# robot_lfy.net
KiCad netlist of a schematic drawn in Altium Designer
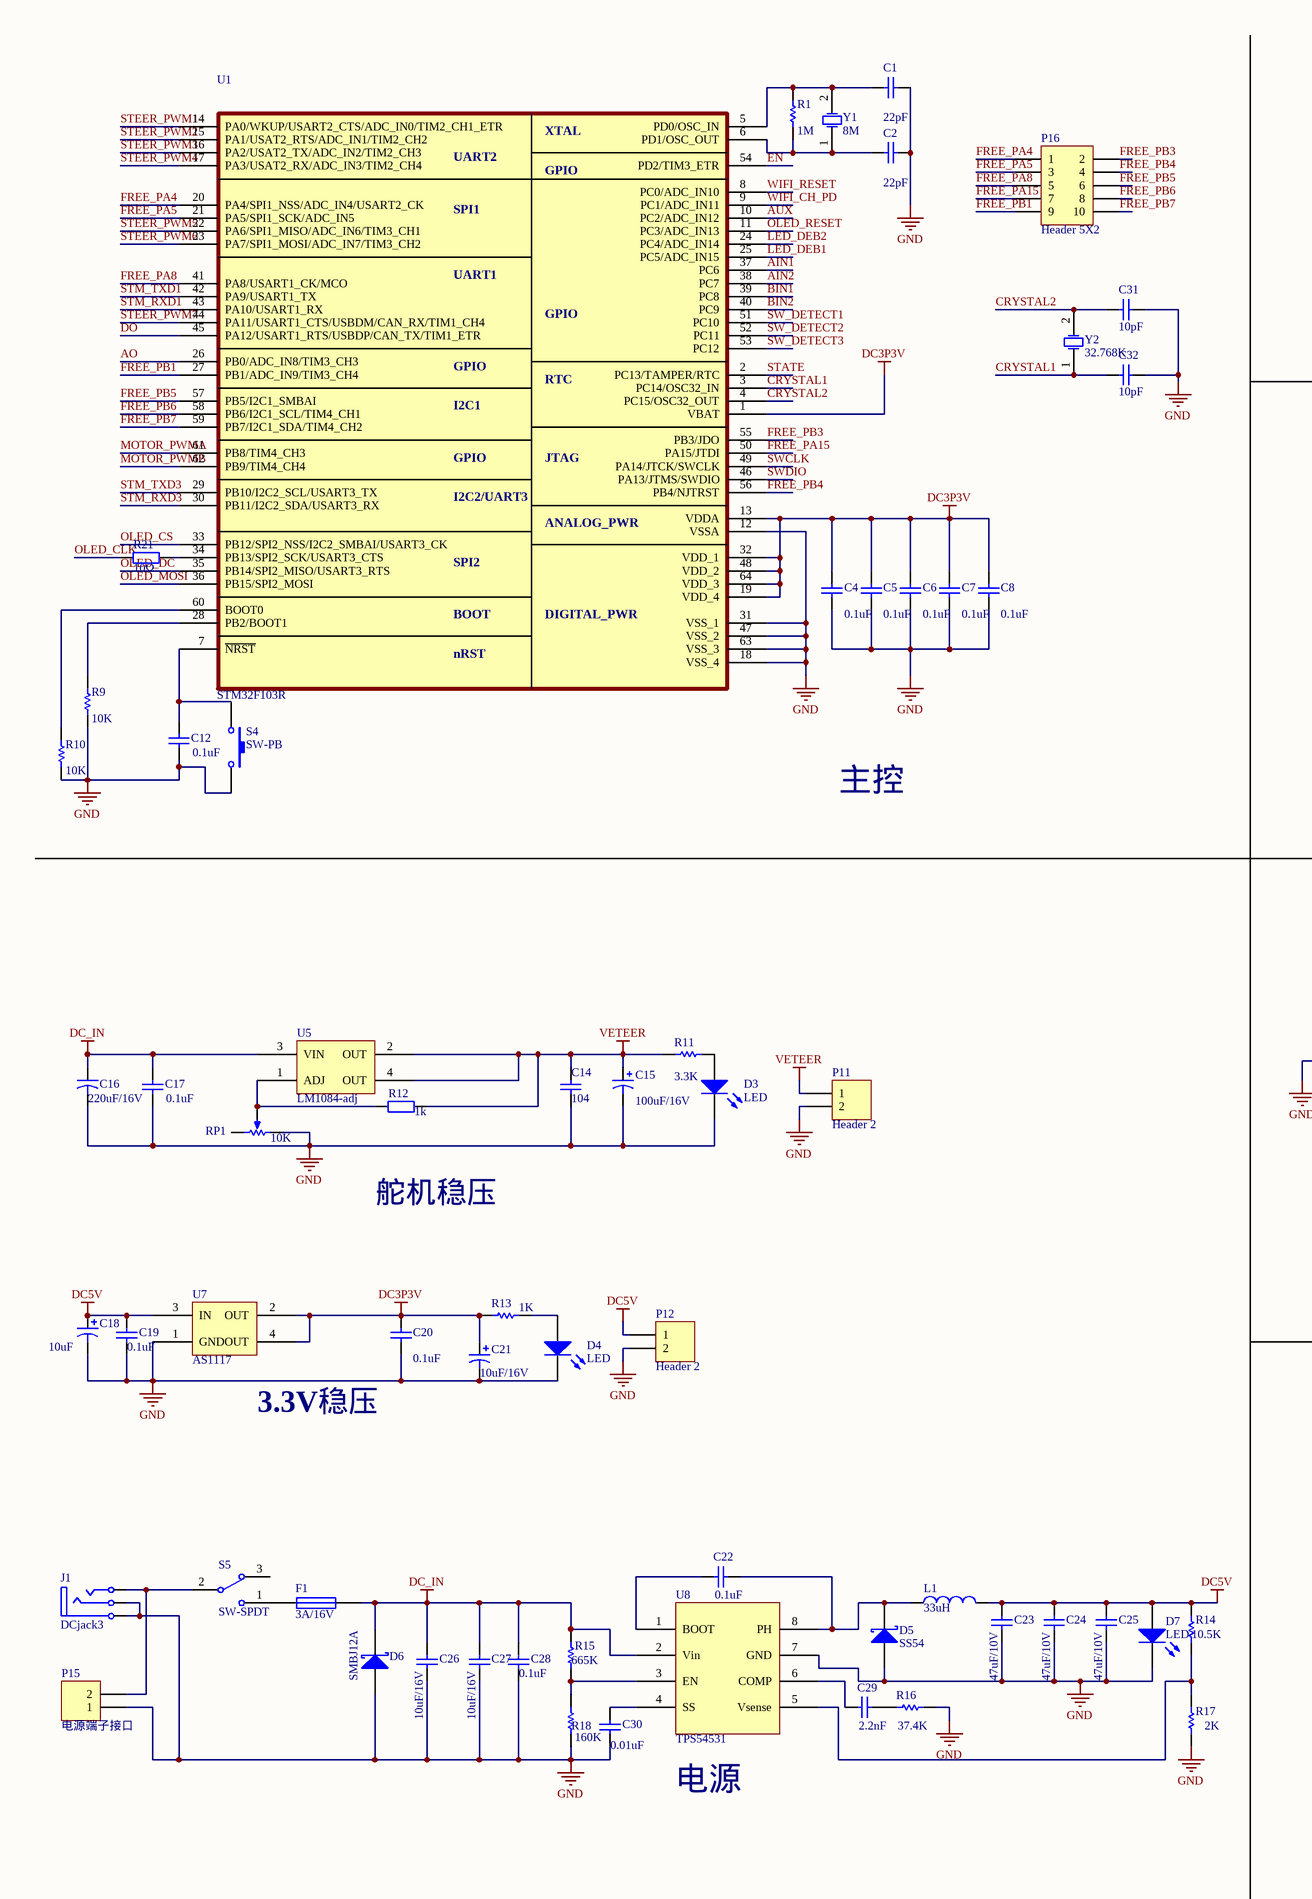
[diagram p0: robot_lfy.SchDoc, left]
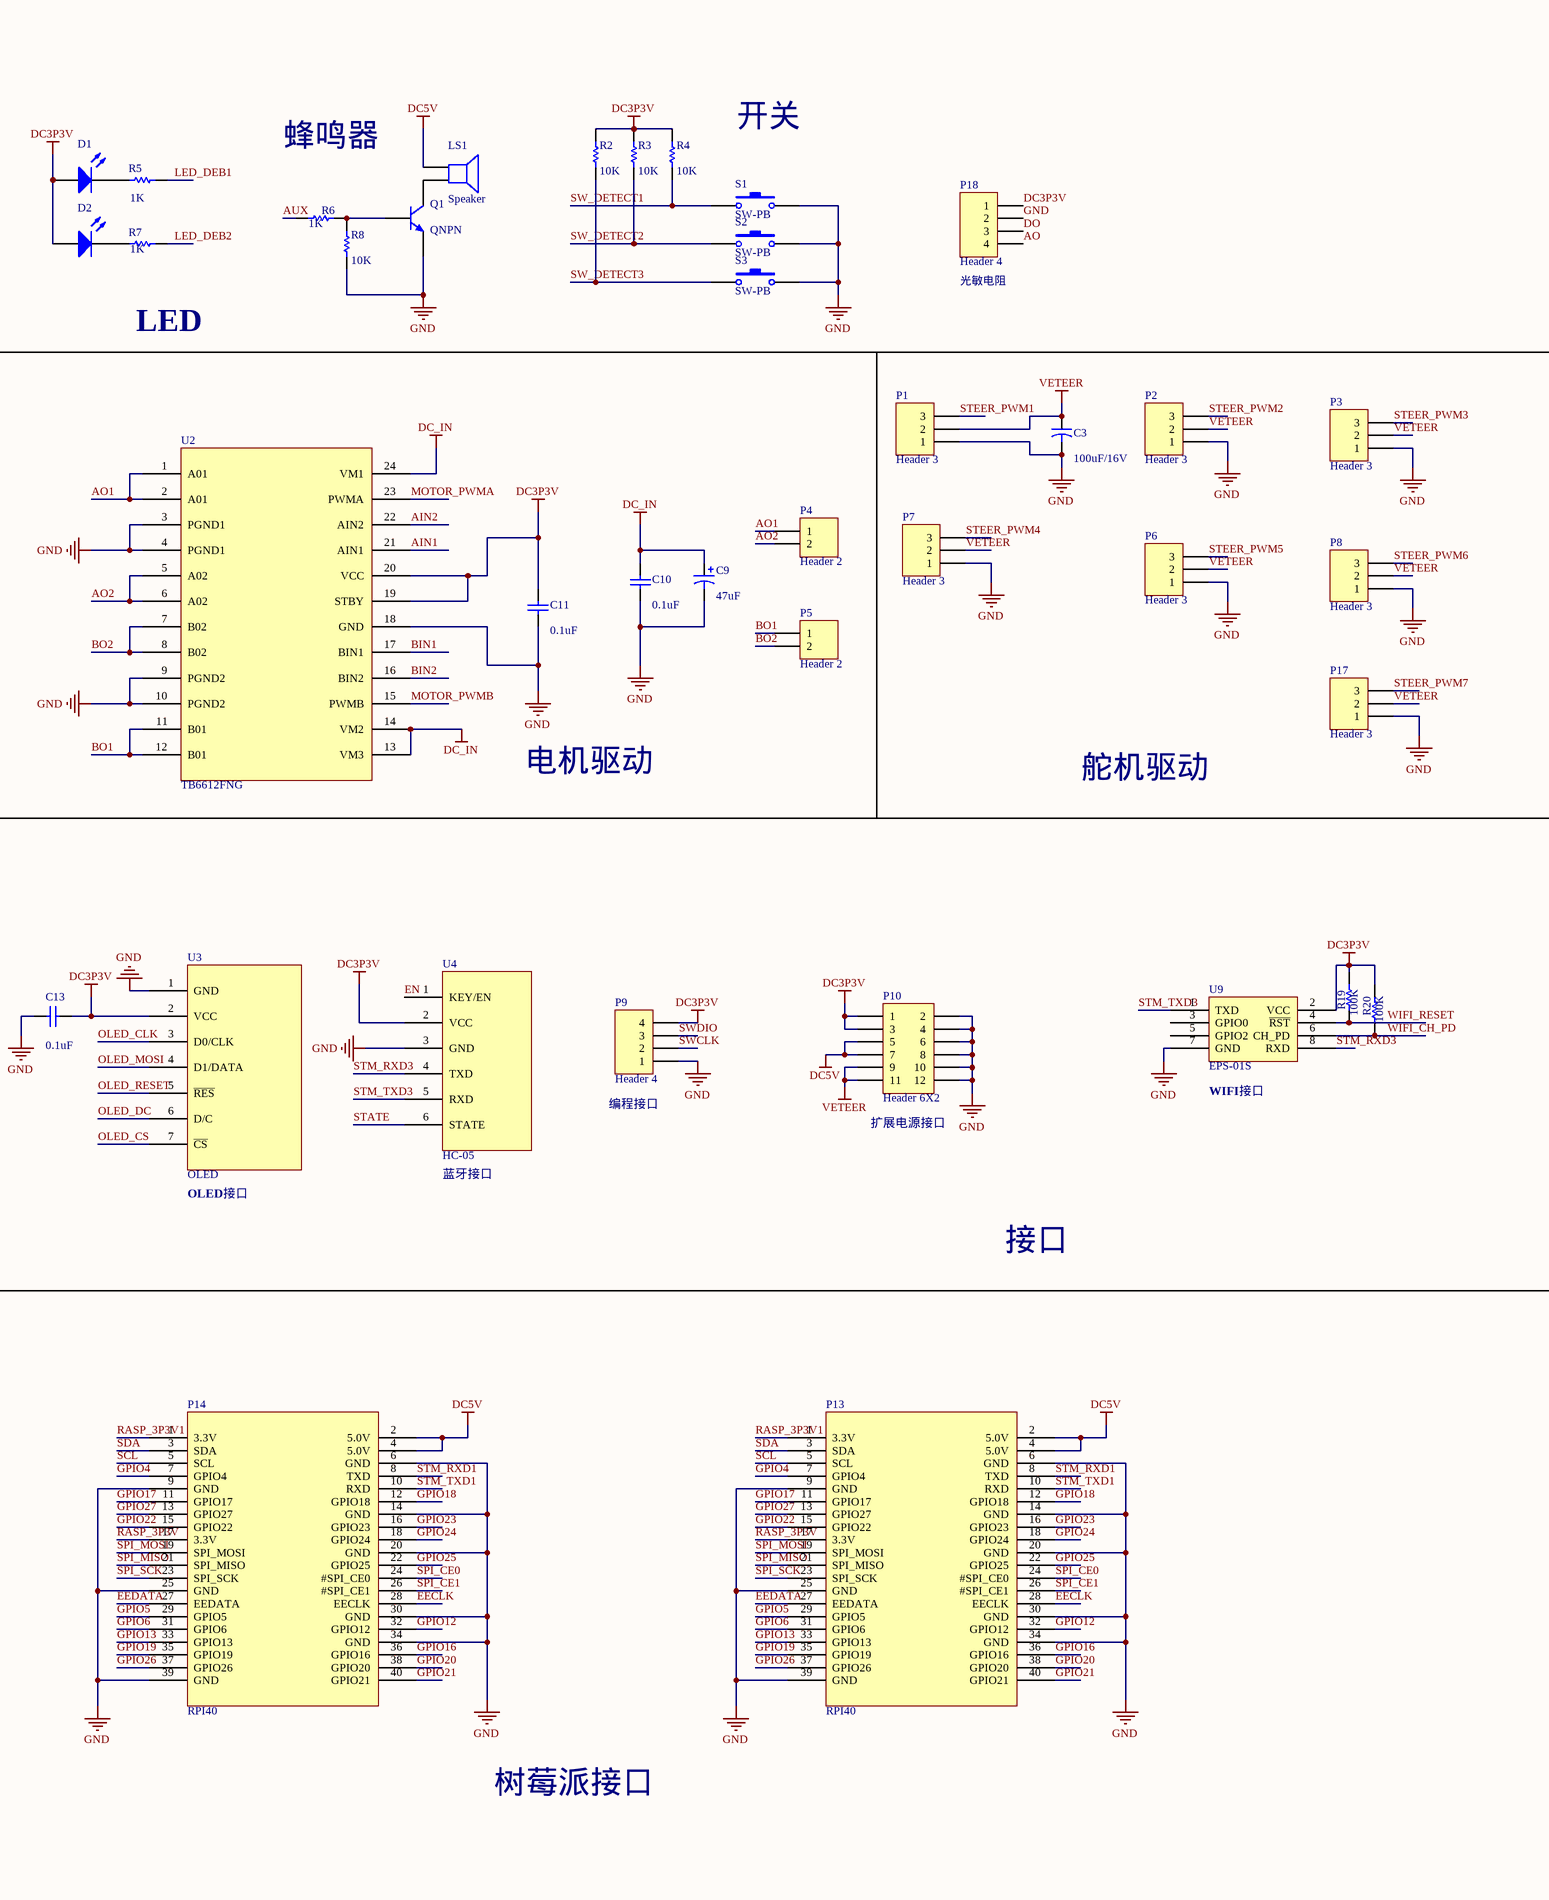
[diagram p1: robot_lfy.SchDoc, right]

(export (version "E")
  (design (tool "Eeschema 10.0.6"))
  (components
    (comp (ref "C1")
      (value "22pF")
      (footprint "LC-0805_C")
      (description "Capacitor")
      (fields (field (name "PUBLISHER") "Altium Limited"))
      (libsource (lib "Miscellaneous Devices") (part "Cap"))
    )
    (comp (ref "C2")
      (value "22pF")
      (footprint "LC-0805_C")
      (description "Capacitor")
      (fields (field (name "PUBLISHER") "Altium Limited"))
      (libsource (lib "Miscellaneous Devices") (part "Cap"))
    )
    (comp (ref "C3")
      (value "100uF/16V")
      (footprint "CM D(6.3*7.7)")
      (description "Capacitor")
      (fields (field (name "PUBLISHER") "Altium Limited"))
      (libsource (lib "Miscellaneous Devices") (part "Cap2"))
    )
    (comp (ref "C4")
      (value "0.1uF")
      (footprint "LC-0805_C")
      (description "Capacitor")
      (fields (field (name "PUBLISHER") "Altium Limited"))
      (libsource (lib "Miscellaneous Devices") (part "Cap"))
    )
    (comp (ref "C5")
      (value "0.1uF")
      (footprint "LC-0805_C")
      (description "Capacitor")
      (fields (field (name "PUBLISHER") "Altium Limited"))
      (libsource (lib "Miscellaneous Devices") (part "Cap"))
    )
    (comp (ref "C6")
      (value "0.1uF")
      (footprint "LC-0805_C")
      (description "Capacitor")
      (fields (field (name "PUBLISHER") "Altium Limited"))
      (libsource (lib "Miscellaneous Devices") (part "Cap"))
    )
    (comp (ref "C7")
      (value "0.1uF")
      (footprint "LC-0805_C")
      (description "Capacitor")
      (fields (field (name "PUBLISHER") "Altium Limited"))
      (libsource (lib "Miscellaneous Devices") (part "Cap"))
    )
    (comp (ref "C8")
      (value "0.1uF")
      (footprint "LC-0805_C")
      (description "Capacitor")
      (fields (field (name "PUBLISHER") "Altium Limited"))
      (libsource (lib "Miscellaneous Devices") (part "Cap"))
    )
    (comp (ref "C9")
      (value "47uF")
      (footprint "LC-1206_C")
      (description "Polarized Capacitor (Surface Mount)")
      (fields (field (name "PUBLISHER") "Altium Limited"))
      (libsource (lib "Miscellaneous Devices") (part "Cap Pol3"))
    )
    (comp (ref "C10")
      (value "0.1uF")
      (footprint "LC-0805_C")
      (description "Capacitor")
      (fields (field (name "PUBLISHER") "Altium Limited"))
      (libsource (lib "Miscellaneous Devices") (part "Cap"))
    )
    (comp (ref "C11")
      (value "0.1uF")
      (footprint "LC-0805_C")
      (description "Capacitor")
      (fields (field (name "PUBLISHER") "Altium Limited"))
      (libsource (lib "Miscellaneous Devices") (part "Cap"))
    )
    (comp (ref "C12")
      (value "0.1uF")
      (footprint "LC-0805_C")
      (description "Capacitor")
      (fields (field (name "PUBLISHER") "Altium Limited"))
      (libsource (lib "Miscellaneous Devices") (part "Cap"))
    )
    (comp (ref "C13")
      (value "0.1uF")
      (footprint "LC-0805_C")
      (description "Capacitor")
      (fields (field (name "PUBLISHER") "Altium Limited"))
      (libsource (lib "Miscellaneous Devices") (part "Cap"))
    )
    (comp (ref "C14")
      (value "104")
      (footprint "LC-0805_C")
      (description "Capacitor")
      (fields (field (name "PUBLISHER") "Altium Limited"))
      (libsource (lib "Miscellaneous Devices") (part "Cap"))
    )
    (comp (ref "C15")
      (value "100uF/16V")
      (footprint "CM D(6.3*7.7)")
      (description "Polarized Capacitor (Radial)")
      (fields (field (name "PUBLISHER") "Altium Limited"))
      (libsource (lib "Miscellaneous Devices") (part "Cap Pol1"))
    )
    (comp (ref "C16")
      (value "220uF/16V")
      (footprint "CM D(6.3*7.7)")
      (description "Capacitor")
      (fields (field (name "PUBLISHER") "Altium Limited"))
      (libsource (lib "Miscellaneous Devices") (part "Cap2"))
    )
    (comp (ref "C17")
      (value "0.1uF")
      (footprint "LC-0805_C")
      (description "Capacitor")
      (fields (field (name "PUBLISHER") "Altium Limited"))
      (libsource (lib "Miscellaneous Devices") (part "Cap"))
    )
    (comp (ref "C18")
      (value "10uF")
      (footprint "LC-1206_C")
      (description "Polarized Capacitor (Radial)")
      (fields (field (name "PUBLISHER") "Altium Limited"))
      (libsource (lib "Miscellaneous Devices") (part "Cap Pol1"))
    )
    (comp (ref "C19")
      (value "0.1uF")
      (footprint "LC-0805_C")
      (description "Capacitor")
      (fields (field (name "PUBLISHER") "Altium Limited"))
      (libsource (lib "Miscellaneous Devices") (part "Cap"))
    )
    (comp (ref "C20")
      (value "0.1uF")
      (footprint "LC-0805_C")
      (description "Capacitor")
      (fields (field (name "PUBLISHER") "Altium Limited"))
      (libsource (lib "Miscellaneous Devices") (part "Cap"))
    )
    (comp (ref "C21")
      (value "10uF/16V")
      (footprint "LC-1206_C")
      (description "Polarized Capacitor (Radial)")
      (fields (field (name "PUBLISHER") "Altium Limited"))
      (libsource (lib "Miscellaneous Devices") (part "Cap Pol1"))
    )
    (comp (ref "C22")
      (value "0.1uF")
      (footprint "LC-0805_C")
      (description "Capacitor")
      (fields (field (name "PUBLISHER") "Altium Limited"))
      (libsource (lib "Miscellaneous Devices") (part "Cap"))
    )
    (comp (ref "C23")
      (value "47uF/10V")
      (footprint "LC-1206_C")
      (description "Capacitor")
      (fields (field (name "PUBLISHER") "Altium Limited"))
      (libsource (lib "Miscellaneous Devices") (part "Cap"))
    )
    (comp (ref "C24")
      (value "47uF/10V")
      (footprint "LC-1206_C")
      (description "Capacitor")
      (fields (field (name "PUBLISHER") "Altium Limited"))
      (libsource (lib "Miscellaneous Devices") (part "Cap"))
    )
    (comp (ref "C25")
      (value "47uF/10V")
      (footprint "LC-1206_C")
      (description "Capacitor")
      (fields (field (name "PUBLISHER") "Altium Limited"))
      (libsource (lib "Miscellaneous Devices") (part "Cap"))
    )
    (comp (ref "C26")
      (value "10uF/16V")
      (footprint "LC-0805_C")
      (description "Capacitor")
      (fields (field (name "PUBLISHER") "Altium Limited"))
      (libsource (lib "Miscellaneous Devices") (part "Cap"))
    )
    (comp (ref "C27")
      (value "10uF/16V")
      (footprint "LC-0805_C")
      (description "Capacitor")
      (fields (field (name "PUBLISHER") "Altium Limited"))
      (libsource (lib "Miscellaneous Devices") (part "Cap"))
    )
    (comp (ref "C28")
      (value "0.1uF")
      (footprint "LC-0805_C")
      (description "Capacitor")
      (fields (field (name "PUBLISHER") "Altium Limited"))
      (libsource (lib "Miscellaneous Devices") (part "Cap"))
    )
    (comp (ref "C29")
      (value "2.2nF")
      (footprint "LC-0805_C")
      (description "Capacitor")
      (fields (field (name "PUBLISHER") "Altium Limited"))
      (libsource (lib "Miscellaneous Devices") (part "Cap"))
    )
    (comp (ref "C30")
      (value "0.01uF")
      (footprint "LC-0805_C")
      (description "Capacitor")
      (fields (field (name "PUBLISHER") "Altium Limited"))
      (libsource (lib "Miscellaneous Devices") (part "Cap"))
    )
    (comp (ref "C31")
      (value "10pF")
      (footprint "LC-0805_C")
      (description "Capacitor")
      (fields (field (name "Comment") "Cap") (field (name "PUBLISHER") "Altium Limited"))
      (libsource (lib "Miscellaneous Devices") (part "Cap"))
    )
    (comp (ref "C32")
      (value "10pF")
      (footprint "LC-0805_C")
      (description "Capacitor")
      (fields (field (name "Comment") "Cap") (field (name "PUBLISHER") "Altium Limited"))
      (libsource (lib "Miscellaneous Devices") (part "Cap"))
    )
    (comp (ref "D1")
      (value "~")
      (footprint "LFY-0805_LED_S1")
      (description "Typical INFRARED GaAs LED")
      (fields (field (name "PUBLISHER") "Altium Limited"))
      (libsource (lib "Miscellaneous Devices") (part "LED0"))
    )
    (comp (ref "D2")
      (value "~")
      (footprint "LFY-0805_LED_S1")
      (description "Typical INFRARED GaAs LED")
      (fields (field (name "PUBLISHER") "Altium Limited"))
      (libsource (lib "Miscellaneous Devices") (part "LED0"))
    )
    (comp (ref "D3")
      (value "LED")
      (footprint "LFY-0805_LED_S1")
      (description "Typical RED, GREEN, YELLOW, AMBER GaAs LED")
      (fields (field (name "PUBLISHER") "Altium Limited"))
      (libsource (lib "Miscellaneous Devices") (part "LED2"))
    )
    (comp (ref "D4")
      (value "LED")
      (footprint "LFY-0805_LED_S1")
      (description "Typical RED, GREEN, YELLOW, AMBER GaAs LED")
      (fields (field (name "PUBLISHER") "Altium Limited"))
      (libsource (lib "Miscellaneous Devices") (part "LED2"))
    )
    (comp (ref "D5")
      (value "SS54")
      (footprint "LFY-SMA(DO-214AC)S2")
      (description "Schottky Diode")
      (fields (field (name "PUBLISHER") "Altium Limited"))
      (libsource (lib "Miscellaneous Devices") (part "D Schottky"))
    )
    (comp (ref "D6")
      (value "SMBJ12A")
      (footprint "LFY-SMA(DO-214AC)S2")
      (description "Schottky Diode")
      (fields (field (name "PUBLISHER") "Altium Limited"))
      (libsource (lib "Miscellaneous Devices") (part "D Schottky"))
    )
    (comp (ref "D7")
      (value "LED")
      (footprint "LFY-0805_LED_S1")
      (description "Typical RED, GREEN, YELLOW, AMBER GaAs LED")
      (fields (field (name "PUBLISHER") "Altium Limited"))
      (libsource (lib "Miscellaneous Devices") (part "LED2"))
    )
    (comp (ref "F1")
      (value "3A/16V")
      (footprint "LFY-1812_F")
      (description "Fuse")
      (fields (field (name "PUBLISHER") "Altium Limited"))
      (libsource (lib "Miscellaneous Devices") (part "Fuse 1"))
    )
    (comp (ref "J1")
      (value "DCjack3")
      (footprint "HDC12")
      (description "Jack Socket, 1/4\" [6.5mm], Thru-Hole, Vertical, 3-Conductor Open Circuit (Non-Normalling)")
      (fields (field (name "PUBLISHER") "Altium Limited"))
      (libsource (lib "Miscellaneous Connectors") (part "Phonejack3"))
    )
    (comp (ref "L1")
      (value "33uH")
      (footprint "LFY-SLO1040H")
      (description "Inductor")
      (fields (field (name "PUBLISHER") "Altium Limited"))
      (libsource (lib "Miscellaneous Devices") (part "Inductor"))
    )
    (comp (ref "LS1")
      (value "Speaker")
      (footprint "BZ")
      (description "Loudspeaker")
      (fields (field (name "PUBLISHER") "Altium Limited"))
      (libsource (lib "Miscellaneous Devices") (part "Speaker"))
    )
    (comp (ref "P1")
      (value "Header 3")
      (footprint "HDR1X3")
      (description "Header, 3-Pin")
      (fields (field (name "PUBLISHER") "Altium Limited"))
      (libsource (lib "Miscellaneous Connectors") (part "Header 3"))
    )
    (comp (ref "P2")
      (value "Header 3")
      (footprint "HDR1X3")
      (description "Header, 3-Pin")
      (fields (field (name "PUBLISHER") "Altium Limited"))
      (libsource (lib "Miscellaneous Connectors") (part "Header 3"))
    )
    (comp (ref "P3")
      (value "Header 3")
      (footprint "HDR1X3")
      (description "Header, 3-Pin")
      (fields (field (name "PUBLISHER") "Altium Limited"))
      (libsource (lib "Miscellaneous Connectors") (part "Header 3"))
    )
    (comp (ref "P4")
      (value "Header 2")
      (footprint "KF508-2P")
      (description "Header, 2-Pin")
      (fields (field (name "PUBLISHER") "Altium Limited"))
      (libsource (lib "Miscellaneous Connectors") (part "Header 2"))
    )
    (comp (ref "P5")
      (value "Header 2")
      (footprint "KF508-2P")
      (description "Header, 2-Pin")
      (fields (field (name "PUBLISHER") "Altium Limited"))
      (libsource (lib "Miscellaneous Connectors") (part "Header 2"))
    )
    (comp (ref "P6")
      (value "Header 3")
      (footprint "HDR1X3")
      (description "Header, 3-Pin")
      (fields (field (name "PUBLISHER") "Altium Limited"))
      (libsource (lib "Miscellaneous Connectors") (part "Header 3"))
    )
    (comp (ref "P7")
      (value "Header 3")
      (footprint "HDR1X3")
      (description "Header, 3-Pin")
      (fields (field (name "PUBLISHER") "Altium Limited"))
      (libsource (lib "Miscellaneous Connectors") (part "Header 3"))
    )
    (comp (ref "P8")
      (value "Header 3")
      (footprint "HDR1X3")
      (description "Header, 3-Pin")
      (fields (field (name "PUBLISHER") "Altium Limited"))
      (libsource (lib "Miscellaneous Connectors") (part "Header 3"))
    )
    (comp (ref "P9")
      (value "Header 4")
      (footprint "HDR1X4")
      (description "Header, 4-Pin")
      (fields (field (name "PUBLISHER") "Altium Limited"))
      (libsource (lib "Miscellaneous Connectors") (part "Header 4"))
    )
    (comp (ref "P10")
      (value "Header 6X2")
      (footprint "HDR2X6")
      (description "Header, 6-Pin, Dual row")
      (fields (field (name "PUBLISHER") "Altium Limited"))
      (libsource (lib "Miscellaneous Connectors") (part "Header 6X2"))
    )
    (comp (ref "P11")
      (value "Header 2")
      (footprint "KF508-2P")
      (description "Header, 2-Pin")
      (fields (field (name "PUBLISHER") "Altium Limited"))
      (libsource (lib "Miscellaneous Connectors") (part "Header 2"))
    )
    (comp (ref "P12")
      (value "Header 2")
      (footprint "KF508-2P")
      (description "Header, 2-Pin")
      (fields (field (name "PUBLISHER") "Altium Limited"))
      (libsource (lib "Miscellaneous Connectors") (part "Header 2"))
    )
    (comp (ref "P13") (value "RPI40") (footprint "HDR2X20") (libsource (lib "User_qxm") (part "RPI40")))
    (comp (ref "P14") (value "RPI40") (footprint "HDR2X20") (libsource (lib "User_qxm") (part "RPI40")))
    (comp (ref "P15")
      (value "电源端子接口")
      (footprint "KF508-2P")
      (description "Header, 2-Pin")
      (fields (field (name "PUBLISHER") "Altium Limited"))
      (libsource (lib "") (part "Header 2_1"))
    )
    (comp (ref "P16")
      (value "Header 5X2")
      (footprint "HDR2X5")
      (description "Header, 5-Pin, Dual row")
      (fields (field (name "PUBLISHER") "Altium Limited"))
      (libsource (lib "Miscellaneous Connectors") (part "Header 5X2"))
    )
    (comp (ref "P17")
      (value "Header 3")
      (footprint "HDR1X3")
      (description "Header, 3-Pin")
      (fields (field (name "PUBLISHER") "Altium Limited"))
      (libsource (lib "Miscellaneous Connectors") (part "Header 3"))
    )
    (comp (ref "P18")
      (value "Header 4")
      (footprint "HDR1X4")
      (description "Header, 4-Pin")
      (fields (field (name "PUBLISHER") "Altium Limited"))
      (libsource (lib "") (part "Header 4_1"))
    )
    (comp (ref "Q1")
      (value "QNPN")
      (footprint "SOT-23B")
      (description "NPN Bipolar Transistor")
      (fields (field (name "PUBLISHER") "Altium Limited"))
      (libsource (lib "Miscellaneous Devices") (part "QNPN"))
    )
    (comp (ref "R1")
      (value "1M")
      (footprint "LC-0805_R")
      (description "Resistor")
      (fields (field (name "PUBLISHER") "Altium Limited"))
      (libsource (lib "Miscellaneous Devices") (part "Res1"))
    )
    (comp (ref "R2")
      (value "10K")
      (footprint "LC-0805_R")
      (description "Resistor")
      (fields (field (name "PUBLISHER") "Altium Limited"))
      (libsource (lib "Miscellaneous Devices") (part "Res1"))
    )
    (comp (ref "R3")
      (value "10K")
      (footprint "LC-0805_R")
      (description "Resistor")
      (fields (field (name "PUBLISHER") "Altium Limited"))
      (libsource (lib "Miscellaneous Devices") (part "Res1"))
    )
    (comp (ref "R4")
      (value "10K")
      (footprint "LC-0805_R")
      (description "Resistor")
      (fields (field (name "PUBLISHER") "Altium Limited"))
      (libsource (lib "Miscellaneous Devices") (part "Res1"))
    )
    (comp (ref "R5")
      (value "1K")
      (footprint "LC-0805_R")
      (description "Resistor")
      (fields (field (name "PUBLISHER") "Altium Limited"))
      (libsource (lib "Miscellaneous Devices") (part "Res1"))
    )
    (comp (ref "R6")
      (value "1K")
      (footprint "LC-0805_R")
      (description "Resistor")
      (fields (field (name "PUBLISHER") "Altium Limited"))
      (libsource (lib "Miscellaneous Devices") (part "Res1"))
    )
    (comp (ref "R7")
      (value "1K")
      (footprint "LC-0805_R")
      (description "Resistor")
      (fields (field (name "PUBLISHER") "Altium Limited"))
      (libsource (lib "Miscellaneous Devices") (part "Res1"))
    )
    (comp (ref "R8")
      (value "10K")
      (footprint "LC-0805_R")
      (description "Resistor")
      (fields (field (name "PUBLISHER") "Altium Limited"))
      (libsource (lib "Miscellaneous Devices") (part "Res1"))
    )
    (comp (ref "R9")
      (value "10K")
      (footprint "LC-0805_R")
      (description "Resistor")
      (fields (field (name "PUBLISHER") "Altium Limited"))
      (libsource (lib "Miscellaneous Devices") (part "Res1"))
    )
    (comp (ref "R10")
      (value "10K")
      (footprint "LC-0805_R")
      (description "Resistor")
      (fields (field (name "PUBLISHER") "Altium Limited"))
      (libsource (lib "Miscellaneous Devices") (part "Res1"))
    )
    (comp (ref "R11")
      (value "3.3K")
      (footprint "LC-0805_R")
      (description "Resistor")
      (fields (field (name "PUBLISHER") "Altium Limited"))
      (libsource (lib "Miscellaneous Devices") (part "Res1"))
    )
    (comp (ref "R12")
      (value "1k")
      (footprint "LC-0805_R")
      (description "Resistor")
      (fields (field (name "PUBLISHER") "Altium Limited"))
      (libsource (lib "Miscellaneous Devices") (part "Res2"))
    )
    (comp (ref "R13")
      (value "1K")
      (footprint "LC-0805_R")
      (description "Resistor")
      (fields (field (name "PUBLISHER") "Altium Limited"))
      (libsource (lib "Miscellaneous Devices") (part "Res1"))
    )
    (comp (ref "R14")
      (value "10.5K")
      (footprint "LC-0805_R")
      (description "Resistor")
      (fields (field (name "PUBLISHER") "Altium Limited"))
      (libsource (lib "Miscellaneous Devices") (part "Res1"))
    )
    (comp (ref "R15")
      (value "665K")
      (footprint "LC-0805_R")
      (description "Resistor")
      (fields (field (name "PUBLISHER") "Altium Limited"))
      (libsource (lib "Miscellaneous Devices") (part "Res1"))
    )
    (comp (ref "R16")
      (value "37.4K")
      (footprint "LC-0805_R")
      (description "Resistor")
      (fields (field (name "PUBLISHER") "Altium Limited"))
      (libsource (lib "Miscellaneous Devices") (part "Res1"))
    )
    (comp (ref "R17")
      (value "2K")
      (footprint "LC-0805_R")
      (description "Resistor")
      (fields (field (name "PUBLISHER") "Altium Limited"))
      (libsource (lib "Miscellaneous Devices") (part "Res1"))
    )
    (comp (ref "R18")
      (value "160K")
      (footprint "LC-0805_R")
      (description "Resistor")
      (fields (field (name "PUBLISHER") "Altium Limited"))
      (libsource (lib "Miscellaneous Devices") (part "Res1"))
    )
    (comp (ref "R19")
      (value "100K")
      (footprint "LC-0805_R")
      (description "Resistor")
      (fields (field (name "PUBLISHER") "Altium Limited"))
      (libsource (lib "Miscellaneous Devices") (part "Res1"))
    )
    (comp (ref "R20")
      (value "100K")
      (footprint "LC-0805_R")
      (description "Resistor")
      (fields (field (name "PUBLISHER") "Altium Limited"))
      (libsource (lib "Miscellaneous Devices") (part "Res1"))
    )
    (comp (ref "R21")
      (value "10Ω")
      (footprint "LC-0805_R")
      (description "Resistor")
      (fields (field (name "Comment") "Res2") (field (name "PUBLISHER") "Altium Limited"))
      (libsource (lib "Miscellaneous Devices") (part "Res2"))
    )
    (comp (ref "RP1") (value "10K") (footprint "LFT-VR-3296") (libsource (lib "own") (part "3296W电位器")))
    (comp (ref "S1")
      (value "SW-PB")
      (footprint "SW-PB2")
      (description "Switch")
      (fields (field (name "PUBLISHER") "Altium Limited"))
      (libsource (lib "Miscellaneous Devices") (part "SW-PB"))
    )
    (comp (ref "S2")
      (value "SW-PB")
      (footprint "SW-PB2")
      (description "Switch")
      (fields (field (name "PUBLISHER") "Altium Limited"))
      (libsource (lib "Miscellaneous Devices") (part "SW-PB"))
    )
    (comp (ref "S3")
      (value "SW-PB")
      (footprint "SW-PB2")
      (description "Switch")
      (fields (field (name "PUBLISHER") "Altium Limited"))
      (libsource (lib "Miscellaneous Devices") (part "SW-PB"))
    )
    (comp (ref "S4")
      (value "SW-PB")
      (footprint "SW-PB2")
      (description "微动开关")
      (fields (field (name "PUBLISHER") "Altium Limited"))
      (libsource (lib "fszhang") (part "SW-PB"))
    )
    (comp (ref "S5")
      (value "SW-SPDT")
      (footprint "LFY-SW-153D6-5")
      (description "SPDT Subminiature Toggle Switch, Right Angle Mounting, Vertical Actuation")
      (fields (field (name "PUBLISHER") "Altium Limited"))
      (libsource (lib "Miscellaneous Devices") (part "SW-SPDT"))
    )
    (comp (ref "U1")
      (value "STM32F103R")
      (footprint "LFY-LQFP64-10*10")
      (libsource (lib "User_qxm") (part "STM32F103R"))
    )
    (comp (ref "U2")
      (value "TB6612FNG")
      (footprint "LFY-SSOP24")
      (libsource (lib "User_qxm") (part "TB6612FNG"))
    )
    (comp (ref "U3") (value "OLED") (footprint "HDR1X7") (libsource (lib "User_qxm") (part "OLED")))
    (comp (ref "U4") (value "HC-05") (libsource (lib "User_lfy") (part "HC-05")))
    (comp (ref "U5")
      (value "LM1084-adj")
      (footprint "LFY-TO263-3")
      (libsource (lib "User_qxm") (part "LM1084-adj"))
    )
    (comp (ref "U7")
      (value "AS1117")
      (footprint "LFY-SOT223")
      (libsource (lib "17160200125-邱祥梅") (part "REG1117-3.3"))
    )
    (comp (ref "U8")
      (value "TPS54531")
      (footprint "LFY-PDSO8")
      (libsource (lib "User_qxm") (part "TPS54531"))
    )
    (comp (ref "U9") (value "EPS-01S") (footprint "HDR2X4") (libsource (lib "User_qxm") (part "EPS-0IS")))
    (comp (ref "Y1")
      (value "8M")
      (footprint "LC-HC-49S")
      (description "Crystal Oscillator")
      (fields (field (name "PUBLISHER") "8M"))
      (libsource (lib "Miscellaneous Devices") (part "XTAL"))
    )
    (comp (ref "Y2")
      (value "32.768K")
      (footprint "LFY-XTAL-8M")
      (description "Crystal Oscillator")
      (fields (field (name "PUBLISHER") "Altium Limited"))
      (libsource (lib "Miscellaneous Devices") (part "XTAL"))
    )
  )
  (nets
    (net (code "1") (name "/AIN1") (class "Default")
      (node (ref "U1") (pin "37") (pinfunction "PC6_37") (pintype "passive"))
      (node (ref "U2") (pin "21") (pinfunction "AIN1_21") (pintype "passive"))
    )
    (net (code "2") (name "/AIN2") (class "Default")
      (node (ref "U1") (pin "38") (pinfunction "PC7_38") (pintype "passive"))
      (node (ref "U2") (pin "22") (pinfunction "AIN2_22") (pintype "passive"))
    )
    (net (code "3") (name "/AO") (class "Default")
      (node (ref "P18") (pin "4") (pinfunction "4_4") (pintype "passive"))
      (node (ref "U1") (pin "26") (pinfunction "PB0/ADC_IN8/TIM3_CH3_26") (pintype "passive"))
    )
    (net (code "4") (name "/AO1") (class "Default")
      (node (ref "P4") (pin "1") (pinfunction "1_1") (pintype "passive"))
      (node (ref "U2") (pin "1") (pinfunction "A01_1") (pintype "passive"))
      (node (ref "U2") (pin "2") (pinfunction "A01_2") (pintype "passive"))
    )
    (net (code "5") (name "/AO2") (class "Default")
      (node (ref "P4") (pin "2") (pinfunction "2_2") (pintype "passive"))
      (node (ref "U2") (pin "5") (pinfunction "A02_5") (pintype "passive"))
      (node (ref "U2") (pin "6") (pinfunction "A02_6") (pintype "passive"))
    )
    (net (code "6") (name "/AUX") (class "Default")
      (node (ref "R6") (pin "1") (pinfunction "1_1") (pintype "passive"))
      (node (ref "U1") (pin "10") (pinfunction "PC2/ADC_IN12_10") (pintype "passive"))
    )
    (net (code "7") (name "/BIN1") (class "Default")
      (node (ref "U1") (pin "39") (pinfunction "PC8_39") (pintype "passive"))
      (node (ref "U2") (pin "17") (pinfunction "BIN1_17") (pintype "passive"))
    )
    (net (code "8") (name "/BIN2") (class "Default")
      (node (ref "U1") (pin "40") (pinfunction "PC9_40") (pintype "passive"))
      (node (ref "U2") (pin "16") (pinfunction "BIN2_16") (pintype "passive"))
    )
    (net (code "9") (name "/BO1") (class "Default")
      (node (ref "P5") (pin "1") (pinfunction "1_1") (pintype "passive"))
      (node (ref "U2") (pin "11") (pinfunction "B01_11") (pintype "passive"))
      (node (ref "U2") (pin "12") (pinfunction "B01_12") (pintype "passive"))
    )
    (net (code "10") (name "/BO2") (class "Default")
      (node (ref "P5") (pin "2") (pinfunction "2_2") (pintype "passive"))
      (node (ref "U2") (pin "7") (pinfunction "B02_7") (pintype "passive"))
      (node (ref "U2") (pin "8") (pinfunction "B02_8") (pintype "passive"))
    )
    (net (code "11") (name "/CRYSTAL1") (class "Default")
      (node (ref "C32") (pin "2") (pinfunction "2_2") (pintype "passive"))
      (node (ref "U1") (pin "3") (pinfunction "PC14/OSC32_IN_3") (pintype "passive"))
      (node (ref "Y2") (pin "1") (pinfunction "OSC1_1") (pintype "passive"))
    )
    (net (code "12") (name "/CRYSTAL2") (class "Default")
      (node (ref "C31") (pin "2") (pinfunction "2_2") (pintype "passive"))
      (node (ref "U1") (pin "4") (pinfunction "PC15/OSC32_OUT_4") (pintype "passive"))
      (node (ref "Y2") (pin "2") (pinfunction "OSC2_2") (pintype "passive"))
    )
    (net (code "13") (name "/DO") (class "Default")
      (node (ref "P18") (pin "3") (pinfunction "3_3") (pintype "passive"))
      (node (ref "U1") (pin "45") (pinfunction "PA12/USART1_RTS/USBDP/CAN_TX/TIM1_ETR_45") (pintype "passive"))
    )
    (net (code "14") (name "/EECLK") (class "Default")
      (node (ref "P13") (pin "28") (pinfunction "EECLK_28") (pintype "passive"))
      (node (ref "P14") (pin "28") (pinfunction "EECLK_28") (pintype "passive"))
    )
    (net (code "15") (name "/EEDATA") (class "Default")
      (node (ref "P13") (pin "27") (pinfunction "EEDATA_27") (pintype "passive"))
      (node (ref "P14") (pin "27") (pinfunction "EEDATA_27") (pintype "passive"))
    )
    (net (code "16") (name "/EN") (class "Default")
      (node (ref "U1") (pin "54") (pinfunction "PD2/TIM3_ETR_54") (pintype "passive"))
      (node (ref "U4") (pin "1") (pinfunction "KEY/EN_1") (pintype "passive"))
    )
    (net (code "17") (name "/FREE_PA4") (class "Default")
      (node (ref "P16") (pin "1") (pinfunction "1_1") (pintype "passive"))
      (node (ref "U1") (pin "20") (pinfunction "PA4/SPI1_NSS/ADC_IN4/USART2_CK_20") (pintype "passive"))
    )
    (net (code "18") (name "/FREE_PA5") (class "Default")
      (node (ref "P16") (pin "3") (pinfunction "3_3") (pintype "passive"))
      (node (ref "U1") (pin "21") (pinfunction "PA5/SPI1_SCK/ADC_IN5_21") (pintype "passive"))
    )
    (net (code "19") (name "/FREE_PA8") (class "Default")
      (node (ref "P16") (pin "5") (pinfunction "5_5") (pintype "passive"))
      (node (ref "U1") (pin "41") (pinfunction "PA8/USART1_CK/MCO_41") (pintype "passive"))
    )
    (net (code "20") (name "/FREE_PA15") (class "Default")
      (node (ref "P16") (pin "7") (pinfunction "7_7") (pintype "passive"))
      (node (ref "U1") (pin "50") (pinfunction "PA15/JTDI_50") (pintype "passive"))
    )
    (net (code "21") (name "/FREE_PB1") (class "Default")
      (node (ref "P16") (pin "9") (pinfunction "9_9") (pintype "passive"))
      (node (ref "U1") (pin "27") (pinfunction "PB1/ADC_IN9/TIM3_CH4_27") (pintype "passive"))
    )
    (net (code "22") (name "/FREE_PB3") (class "Default")
      (node (ref "P16") (pin "2") (pinfunction "2_2") (pintype "passive"))
      (node (ref "U1") (pin "55") (pinfunction "PB3/JDO_55") (pintype "passive"))
    )
    (net (code "23") (name "/FREE_PB4") (class "Default")
      (node (ref "P16") (pin "4") (pinfunction "4_4") (pintype "passive"))
      (node (ref "U1") (pin "56") (pinfunction "PB4/NJTRST_56") (pintype "passive"))
    )
    (net (code "24") (name "/FREE_PB5") (class "Default")
      (node (ref "P16") (pin "6") (pinfunction "6_6") (pintype "passive"))
      (node (ref "U1") (pin "57") (pinfunction "PB5/I2C1_SMBAI_57") (pintype "passive"))
    )
    (net (code "25") (name "/FREE_PB6") (class "Default")
      (node (ref "P16") (pin "8") (pinfunction "8_8") (pintype "passive"))
      (node (ref "U1") (pin "58") (pinfunction "PB6/I2C1_SCL/TIM4_CH1_58") (pintype "passive"))
    )
    (net (code "26") (name "/FREE_PB7") (class "Default")
      (node (ref "P16") (pin "10") (pinfunction "10_10") (pintype "passive"))
      (node (ref "U1") (pin "59") (pinfunction "PB7/I2C1_SDA/TIM4_CH2_59") (pintype "passive"))
    )
    (net (code "27") (name "/GPIO4") (class "Default")
      (node (ref "P13") (pin "7") (pinfunction "GPIO4_7") (pintype "passive"))
      (node (ref "P14") (pin "7") (pinfunction "GPIO4_7") (pintype "passive"))
    )
    (net (code "28") (name "/GPIO5") (class "Default")
      (node (ref "P13") (pin "29") (pinfunction "GPIO5_29") (pintype "passive"))
      (node (ref "P14") (pin "29") (pinfunction "GPIO5_29") (pintype "passive"))
    )
    (net (code "29") (name "/GPIO6") (class "Default")
      (node (ref "P13") (pin "31") (pinfunction "GPIO6_31") (pintype "passive"))
      (node (ref "P14") (pin "31") (pinfunction "GPIO6_31") (pintype "passive"))
    )
    (net (code "30") (name "/GPIO12") (class "Default")
      (node (ref "P13") (pin "32") (pinfunction "GPIO12_32") (pintype "passive"))
      (node (ref "P14") (pin "32") (pinfunction "GPIO12_32") (pintype "passive"))
    )
    (net (code "31") (name "/GPIO13") (class "Default")
      (node (ref "P13") (pin "33") (pinfunction "GPIO13_33") (pintype "passive"))
      (node (ref "P14") (pin "33") (pinfunction "GPIO13_33") (pintype "passive"))
    )
    (net (code "32") (name "/GPIO16") (class "Default")
      (node (ref "P13") (pin "36") (pinfunction "GPIO16_36") (pintype "passive"))
      (node (ref "P14") (pin "36") (pinfunction "GPIO16_36") (pintype "passive"))
    )
    (net (code "33") (name "/GPIO17") (class "Default")
      (node (ref "P13") (pin "11") (pinfunction "GPIO17_11") (pintype "passive"))
      (node (ref "P14") (pin "11") (pinfunction "GPIO17_11") (pintype "passive"))
    )
    (net (code "34") (name "/GPIO18") (class "Default")
      (node (ref "P13") (pin "12") (pinfunction "GPIO18_12") (pintype "passive"))
      (node (ref "P14") (pin "12") (pinfunction "GPIO18_12") (pintype "passive"))
    )
    (net (code "35") (name "/GPIO19") (class "Default")
      (node (ref "P13") (pin "35") (pinfunction "GPIO19_35") (pintype "passive"))
      (node (ref "P14") (pin "35") (pinfunction "GPIO19_35") (pintype "passive"))
    )
    (net (code "36") (name "/GPIO20") (class "Default")
      (node (ref "P13") (pin "38") (pinfunction "GPIO20_38") (pintype "passive"))
      (node (ref "P14") (pin "38") (pinfunction "GPIO20_38") (pintype "passive"))
    )
    (net (code "37") (name "/GPIO21") (class "Default")
      (node (ref "P13") (pin "40") (pinfunction "GPIO21_40") (pintype "passive"))
      (node (ref "P14") (pin "40") (pinfunction "GPIO21_40") (pintype "passive"))
    )
    (net (code "38") (name "/GPIO22") (class "Default")
      (node (ref "P13") (pin "15") (pinfunction "GPIO22_15") (pintype "passive"))
      (node (ref "P14") (pin "15") (pinfunction "GPIO22_15") (pintype "passive"))
    )
    (net (code "39") (name "/GPIO23") (class "Default")
      (node (ref "P13") (pin "16") (pinfunction "GPIO23_16") (pintype "passive"))
      (node (ref "P14") (pin "16") (pinfunction "GPIO23_16") (pintype "passive"))
    )
    (net (code "40") (name "/GPIO24") (class "Default")
      (node (ref "P13") (pin "18") (pinfunction "GPIO24_18") (pintype "passive"))
      (node (ref "P14") (pin "18") (pinfunction "GPIO24_18") (pintype "passive"))
    )
    (net (code "41") (name "/GPIO25") (class "Default")
      (node (ref "P13") (pin "22") (pinfunction "GPIO25_22") (pintype "passive"))
      (node (ref "P14") (pin "22") (pinfunction "GPIO25_22") (pintype "passive"))
    )
    (net (code "42") (name "/GPIO26") (class "Default")
      (node (ref "P13") (pin "37") (pinfunction "GPIO26_37") (pintype "passive"))
      (node (ref "P14") (pin "37") (pinfunction "GPIO26_37") (pintype "passive"))
    )
    (net (code "43") (name "/GPIO27") (class "Default")
      (node (ref "P13") (pin "13") (pinfunction "GPIO27_13") (pintype "passive"))
      (node (ref "P14") (pin "13") (pinfunction "GPIO27_13") (pintype "passive"))
    )
    (net (code "44") (name "/LED_DEB1") (class "Default")
      (node (ref "R5") (pin "2") (pinfunction "2_2") (pintype "passive"))
      (node (ref "U1") (pin "25") (pinfunction "PC5/ADC_IN15_25") (pintype "passive"))
    )
    (net (code "45") (name "/LED_DEB2") (class "Default")
      (node (ref "R7") (pin "2") (pinfunction "2_2") (pintype "passive"))
      (node (ref "U1") (pin "24") (pinfunction "PC4/ADC_IN14_24") (pintype "passive"))
    )
    (net (code "46") (name "/MOTOR_PWMA") (class "Default")
      (node (ref "U1") (pin "61") (pinfunction "PB8/TIM4_CH3_61") (pintype "passive"))
      (node (ref "U2") (pin "23") (pinfunction "PWMA_23") (pintype "passive"))
    )
    (net (code "47") (name "/MOTOR_PWMB") (class "Default")
      (node (ref "U1") (pin "62") (pinfunction "PB9/TIM4_CH4_62") (pintype "passive"))
      (node (ref "U2") (pin "15") (pinfunction "PWMB_15") (pintype "passive"))
    )
    (net (code "48") (name "/OLED_CLK") (class "Default")
      (node (ref "R21") (pin "2") (pinfunction "2_2") (pintype "passive"))
      (node (ref "U3") (pin "3") (pinfunction "D0/CLK_3") (pintype "passive"))
    )
    (net (code "49") (name "/OLED_CS") (class "Default")
      (node (ref "U1") (pin "33") (pinfunction "PB12/SPI2_NSS/I2C2_SMBAI/USART3_CK_33") (pintype "passive"))
      (node (ref "U3") (pin "7") (pinfunction "~{CS}_7") (pintype "passive"))
    )
    (net (code "50") (name "/OLED_DC") (class "Default")
      (node (ref "U1") (pin "35") (pinfunction "PB14/SPI2_MISO/USART3_RTS_35") (pintype "passive"))
      (node (ref "U3") (pin "6") (pinfunction "D/C_6") (pintype "passive"))
    )
    (net (code "51") (name "/OLED_MOSI") (class "Default")
      (node (ref "U1") (pin "36") (pinfunction "PB15/SPI2_MOSI_36") (pintype "passive"))
      (node (ref "U3") (pin "4") (pinfunction "D1/DATA_4") (pintype "passive"))
    )
    (net (code "52") (name "/OLED_RESET") (class "Default")
      (node (ref "U1") (pin "11") (pinfunction "PC3/ADC_IN13_11") (pintype "passive"))
      (node (ref "U3") (pin "5") (pinfunction "~{RES}_5") (pintype "passive"))
    )
    (net (code "53") (name "/RASP_3P3V") (class "Default")
      (node (ref "P13") (pin "17") (pinfunction "3.3V_17") (pintype "passive"))
      (node (ref "P14") (pin "17") (pinfunction "3.3V_17") (pintype "passive"))
    )
    (net (code "54") (name "/RASP_3P3V1") (class "Default")
      (node (ref "P13") (pin "1") (pinfunction "3.3V_1") (pintype "passive"))
      (node (ref "P14") (pin "1") (pinfunction "3.3V_1") (pintype "passive"))
    )
    (net (code "55") (name "/SCL") (class "Default")
      (node (ref "P13") (pin "5") (pinfunction "SCL_5") (pintype "passive"))
      (node (ref "P14") (pin "5") (pinfunction "SCL_5") (pintype "passive"))
    )
    (net (code "56") (name "/SDA") (class "Default")
      (node (ref "P13") (pin "3") (pinfunction "SDA_3") (pintype "passive"))
      (node (ref "P14") (pin "3") (pinfunction "SDA_3") (pintype "passive"))
    )
    (net (code "57") (name "/SPI_CE0") (class "Default")
      (node (ref "P13") (pin "24") (pinfunction "#SPI_CE0_24") (pintype "passive"))
      (node (ref "P14") (pin "24") (pinfunction "#SPI_CE0_24") (pintype "passive"))
    )
    (net (code "58") (name "/SPI_CE1") (class "Default")
      (node (ref "P13") (pin "26") (pinfunction "#SPI_CE1_26") (pintype "passive"))
      (node (ref "P14") (pin "26") (pinfunction "#SPI_CE1_26") (pintype "passive"))
    )
    (net (code "59") (name "/SPI_MISO") (class "Default")
      (node (ref "P13") (pin "21") (pinfunction "SPI_MISO_21") (pintype "passive"))
      (node (ref "P14") (pin "21") (pinfunction "SPI_MISO_21") (pintype "passive"))
    )
    (net (code "60") (name "/SPI_MOSI") (class "Default")
      (node (ref "P13") (pin "19") (pinfunction "SPI_MOSI_19") (pintype "passive"))
      (node (ref "P14") (pin "19") (pinfunction "SPI_MOSI_19") (pintype "passive"))
    )
    (net (code "61") (name "/SPI_SCK") (class "Default")
      (node (ref "P13") (pin "23") (pinfunction "SPI_SCK_23") (pintype "passive"))
      (node (ref "P14") (pin "23") (pinfunction "SPI_SCK_23") (pintype "passive"))
    )
    (net (code "62") (name "/STATE") (class "Default")
      (node (ref "U1") (pin "2") (pinfunction "PC13/TAMPER/RTC_2") (pintype "passive"))
      (node (ref "U4") (pin "6") (pinfunction "STATE_6") (pintype "passive"))
    )
    (net (code "63") (name "/STEER_PWM1") (class "Default")
      (node (ref "P1") (pin "3") (pinfunction "3_3") (pintype "passive"))
      (node (ref "U1") (pin "14") (pinfunction "PA0/WKUP/USART2_CTS/ADC_IN0/TIM2_CH1_ETR_14") (pintype "passive"))
    )
    (net (code "64") (name "/STEER_PWM2") (class "Default")
      (node (ref "P2") (pin "3") (pinfunction "3_3") (pintype "passive"))
      (node (ref "U1") (pin "15") (pinfunction "PA1/USAT2_RTS/ADC_IN1/TIM2_CH2_15") (pintype "passive"))
    )
    (net (code "65") (name "/STEER_PWM3") (class "Default")
      (node (ref "P3") (pin "3") (pinfunction "3_3") (pintype "passive"))
      (node (ref "U1") (pin "16") (pinfunction "PA2/USAT2_TX/ADC_IN2/TIM2_CH3_16") (pintype "passive"))
    )
    (net (code "66") (name "/STEER_PWM4") (class "Default")
      (node (ref "P7") (pin "3") (pinfunction "3_3") (pintype "passive"))
      (node (ref "U1") (pin "17") (pinfunction "PA3/USAT2_RX/ADC_IN3/TIM2_CH4_17") (pintype "passive"))
    )
    (net (code "67") (name "/STEER_PWM5") (class "Default")
      (node (ref "P6") (pin "3") (pinfunction "3_3") (pintype "passive"))
      (node (ref "U1") (pin "22") (pinfunction "PA6/SPI1_MISO/ADC_IN6/TIM3_CH1_22") (pintype "passive"))
    )
    (net (code "68") (name "/STEER_PWM6") (class "Default")
      (node (ref "P8") (pin "3") (pinfunction "3_3") (pintype "passive"))
      (node (ref "U1") (pin "23") (pinfunction "PA7/SPI1_MOSI/ADC_IN7/TIM3_CH2_23") (pintype "passive"))
    )
    (net (code "69") (name "/STEER_PWM7") (class "Default")
      (node (ref "P17") (pin "3") (pinfunction "3_3") (pintype "passive"))
      (node (ref "U1") (pin "44") (pinfunction "PA11/USART1_CTS/USBDM/CAN_RX/TIM1_CH4_44") (pintype "passive"))
    )
    (net (code "70") (name "/STM_RXD1") (class "Default")
      (node (ref "P13") (pin "8") (pinfunction "TXD_8") (pintype "passive"))
      (node (ref "P14") (pin "8") (pinfunction "TXD_8") (pintype "passive"))
      (node (ref "U1") (pin "43") (pinfunction "PA10/USART1_RX_43") (pintype "passive"))
    )
    (net (code "71") (name "/STM_RXD3") (class "Default")
      (node (ref "U1") (pin "30") (pinfunction "PB11/I2C2_SDA/USART3_RX_30") (pintype "passive"))
      (node (ref "U4") (pin "4") (pinfunction "TXD_4") (pintype "passive"))
      (node (ref "U9") (pin "8") (pinfunction "RXD_8") (pintype "passive"))
    )
    (net (code "72") (name "/STM_TXD1") (class "Default")
      (node (ref "P13") (pin "10") (pinfunction "RXD_10") (pintype "passive"))
      (node (ref "P14") (pin "10") (pinfunction "RXD_10") (pintype "passive"))
      (node (ref "U1") (pin "42") (pinfunction "PA9/USART1_TX_42") (pintype "passive"))
    )
    (net (code "73") (name "/STM_TXD3") (class "Default")
      (node (ref "U1") (pin "29") (pinfunction "PB10/I2C2_SCL/USART3_TX_29") (pintype "passive"))
      (node (ref "U4") (pin "5") (pinfunction "RXD_5") (pintype "passive"))
      (node (ref "U9") (pin "1") (pinfunction "TXD_1") (pintype "passive"))
    )
    (net (code "74") (name "/SWCLK") (class "Default")
      (node (ref "P9") (pin "2") (pinfunction "2_2") (pintype "passive"))
      (node (ref "U1") (pin "49") (pinfunction "PA14/JTCK/SWCLK_49") (pintype "passive"))
    )
    (net (code "75") (name "/SWDIO") (class "Default")
      (node (ref "P9") (pin "3") (pinfunction "3_3") (pintype "passive"))
      (node (ref "U1") (pin "46") (pinfunction "PA13/JTMS/SWDIO_46") (pintype "passive"))
    )
    (net (code "76") (name "/SW_DETECT1") (class "Default")
      (node (ref "R4") (pin "1") (pinfunction "1_1") (pintype "passive"))
      (node (ref "S1") (pin "1") (pinfunction "1_1") (pintype "passive"))
      (node (ref "U1") (pin "51") (pinfunction "PC10_51") (pintype "passive"))
    )
    (net (code "77") (name "/SW_DETECT2") (class "Default")
      (node (ref "R3") (pin "1") (pinfunction "1_1") (pintype "passive"))
      (node (ref "S2") (pin "1") (pinfunction "1_1") (pintype "passive"))
      (node (ref "U1") (pin "52") (pinfunction "PC11_52") (pintype "passive"))
    )
    (net (code "78") (name "/SW_DETECT3") (class "Default")
      (node (ref "R2") (pin "1") (pinfunction "1_1") (pintype "passive"))
      (node (ref "S3") (pin "1") (pinfunction "1_1") (pintype "passive"))
      (node (ref "U1") (pin "53") (pinfunction "PC12_53") (pintype "passive"))
    )
    (net (code "79") (name "/WIFI_CH_PD") (class "Default")
      (node (ref "R20") (pin "2") (pinfunction "2_2") (pintype "passive"))
      (node (ref "U1") (pin "9") (pinfunction "PC1/ADC_IN11_9") (pintype "passive"))
      (node (ref "U9") (pin "6") (pinfunction "CH_PD_6") (pintype "passive"))
    )
    (net (code "80") (name "/WIFI_RESET") (class "Default")
      (node (ref "R19") (pin "2") (pinfunction "2_2") (pintype "passive"))
      (node (ref "U1") (pin "8") (pinfunction "PC0/ADC_IN10_8") (pintype "passive"))
      (node (ref "U9") (pin "4") (pinfunction "~{RST}_4") (pintype "passive"))
    )
    (net (code "81") (name "DC3P3V") (class "Default")
      (node (ref "C11") (pin "2") (pinfunction "2_2") (pintype "passive"))
      (node (ref "C13") (pin "2") (pinfunction "2_2") (pintype "passive"))
      (node (ref "C20") (pin "2") (pinfunction "2_2") (pintype "passive"))
      (node (ref "C21") (pin "1") (pinfunction "1_1") (pintype "passive"))
      (node (ref "C4") (pin "2") (pinfunction "2_2") (pintype "passive"))
      (node (ref "C5") (pin "2") (pinfunction "2_2") (pintype "passive"))
      (node (ref "C6") (pin "2") (pinfunction "2_2") (pintype "passive"))
      (node (ref "C7") (pin "2") (pinfunction "2_2") (pintype "passive"))
      (node (ref "C8") (pin "2") (pinfunction "2_2") (pintype "passive"))
      (node (ref "D1") (pin "1") (pinfunction "A_1") (pintype "passive"))
      (node (ref "D2") (pin "1") (pinfunction "A_1") (pintype "passive"))
      (node (ref "P10") (pin "1") (pinfunction "1_1") (pintype "passive"))
      (node (ref "P10") (pin "3") (pinfunction "3_3") (pintype "passive"))
      (node (ref "P18") (pin "1") (pinfunction "1_1") (pintype "passive"))
      (node (ref "P9") (pin "4") (pinfunction "4_4") (pintype "passive"))
      (node (ref "R13") (pin "1") (pinfunction "1_1") (pintype "passive"))
      (node (ref "R19") (pin "1") (pinfunction "1_1") (pintype "passive"))
      (node (ref "R2") (pin "2") (pinfunction "2_2") (pintype "passive"))
      (node (ref "R20") (pin "1") (pinfunction "1_1") (pintype "passive"))
      (node (ref "R3") (pin "2") (pinfunction "2_2") (pintype "passive"))
      (node (ref "R4") (pin "2") (pinfunction "2_2") (pintype "passive"))
      (node (ref "U1") (pin "1") (pinfunction "VBAT_1") (pintype "passive"))
      (node (ref "U1") (pin "13") (pinfunction "VDDA_13") (pintype "passive"))
      (node (ref "U1") (pin "19") (pinfunction "VDD_4_19") (pintype "passive"))
      (node (ref "U1") (pin "32") (pinfunction "VDD_1_32") (pintype "passive"))
      (node (ref "U1") (pin "48") (pinfunction "VDD_2_48") (pintype "passive"))
      (node (ref "U1") (pin "64") (pinfunction "VDD_3_64") (pintype "passive"))
      (node (ref "U2") (pin "19") (pinfunction "STBY_19") (pintype "passive"))
      (node (ref "U2") (pin "20") (pinfunction "VCC_20") (pintype "passive"))
      (node (ref "U3") (pin "2") (pinfunction "VCC_2") (pintype "passive"))
      (node (ref "U4") (pin "2") (pinfunction "VCC_2") (pintype "passive"))
      (node (ref "U7") (pin "2") (pinfunction "OUT_2") (pintype "power_in"))
      (node (ref "U7") (pin "4") (pinfunction "OUT_4") (pintype "power_in"))
      (node (ref "U9") (pin "2") (pinfunction "VCC_2") (pintype "passive"))
    )
    (net (code "82") (name "DC5V") (class "Default")
      (node (ref "C18") (pin "1") (pinfunction "1_1") (pintype "passive"))
      (node (ref "C19") (pin "2") (pinfunction "2_2") (pintype "passive"))
      (node (ref "C23") (pin "1") (pinfunction "1_1") (pintype "passive"))
      (node (ref "C24") (pin "1") (pinfunction "1_1") (pintype "passive"))
      (node (ref "C25") (pin "1") (pinfunction "1_1") (pintype "passive"))
      (node (ref "D7") (pin "1") (pinfunction "A_1") (pintype "passive"))
      (node (ref "L1") (pin "2") (pinfunction "2_2") (pintype "passive"))
      (node (ref "LS1") (pin "1") (pinfunction "1_1") (pintype "passive"))
      (node (ref "P10") (pin "5") (pinfunction "5_5") (pintype "passive"))
      (node (ref "P10") (pin "7") (pinfunction "7_7") (pintype "passive"))
      (node (ref "P12") (pin "1") (pinfunction "1_1") (pintype "passive"))
      (node (ref "P13") (pin "2") (pinfunction "5.0V_2") (pintype "passive"))
      (node (ref "P13") (pin "4") (pinfunction "5.0V_4") (pintype "passive"))
      (node (ref "P14") (pin "2") (pinfunction "5.0V_2") (pintype "passive"))
      (node (ref "P14") (pin "4") (pinfunction "5.0V_4") (pintype "passive"))
      (node (ref "R14") (pin "2") (pinfunction "2_2") (pintype "passive"))
      (node (ref "U7") (pin "3") (pinfunction "IN_3") (pintype "power_in"))
    )
    (net (code "83") (name "DC_IN") (class "Default")
      (node (ref "C10") (pin "2") (pinfunction "2_2") (pintype "passive"))
      (node (ref "C16") (pin "1") (pinfunction "1_1") (pintype "passive"))
      (node (ref "C17") (pin "2") (pinfunction "2_2") (pintype "passive"))
      (node (ref "C26") (pin "2") (pinfunction "2_2") (pintype "passive"))
      (node (ref "C27") (pin "2") (pinfunction "2_2") (pintype "passive"))
      (node (ref "C28") (pin "2") (pinfunction "2_2") (pintype "passive"))
      (node (ref "C9") (pin "1") (pinfunction "1_1") (pintype "passive"))
      (node (ref "D6") (pin "2") (pinfunction "K_2") (pintype "passive"))
      (node (ref "F1") (pin "2") (pinfunction "2_2") (pintype "passive"))
      (node (ref "R15") (pin "2") (pinfunction "2_2") (pintype "passive"))
      (node (ref "U2") (pin "13") (pinfunction "VM3_13") (pintype "passive"))
      (node (ref "U2") (pin "14") (pinfunction "VM2_14") (pintype "passive"))
      (node (ref "U2") (pin "24") (pinfunction "VM1_24") (pintype "passive"))
      (node (ref "U5") (pin "3") (pinfunction "VIN_3") (pintype "passive"))
      (node (ref "U8") (pin "2") (pinfunction "Vin_2") (pintype "passive"))
    )
    (net (code "84") (name "GND") (class "Default")
      (node (ref "C1") (pin "2") (pinfunction "2_2") (pintype "passive"))
      (node (ref "C10") (pin "1") (pinfunction "1_1") (pintype "passive"))
      (node (ref "C11") (pin "1") (pinfunction "1_1") (pintype "passive"))
      (node (ref "C12") (pin "1") (pinfunction "1_1") (pintype "passive"))
      (node (ref "C13") (pin "1") (pinfunction "1_1") (pintype "passive"))
      (node (ref "C14") (pin "1") (pinfunction "1_1") (pintype "passive"))
      (node (ref "C15") (pin "2") (pinfunction "2_2") (pintype "passive"))
      (node (ref "C16") (pin "2") (pinfunction "2_2") (pintype "passive"))
      (node (ref "C17") (pin "1") (pinfunction "1_1") (pintype "passive"))
      (node (ref "C18") (pin "2") (pinfunction "2_2") (pintype "passive"))
      (node (ref "C19") (pin "1") (pinfunction "1_1") (pintype "passive"))
      (node (ref "C2") (pin "2") (pinfunction "2_2") (pintype "passive"))
      (node (ref "C20") (pin "1") (pinfunction "1_1") (pintype "passive"))
      (node (ref "C21") (pin "2") (pinfunction "2_2") (pintype "passive"))
      (node (ref "C23") (pin "2") (pinfunction "2_2") (pintype "passive"))
      (node (ref "C24") (pin "2") (pinfunction "2_2") (pintype "passive"))
      (node (ref "C25") (pin "2") (pinfunction "2_2") (pintype "passive"))
      (node (ref "C26") (pin "1") (pinfunction "1_1") (pintype "passive"))
      (node (ref "C27") (pin "1") (pinfunction "1_1") (pintype "passive"))
      (node (ref "C28") (pin "1") (pinfunction "1_1") (pintype "passive"))
      (node (ref "C3") (pin "2") (pinfunction "2_2") (pintype "passive"))
      (node (ref "C30") (pin "1") (pinfunction "1_1") (pintype "passive"))
      (node (ref "C31") (pin "1") (pinfunction "1_1") (pintype "passive"))
      (node (ref "C32") (pin "1") (pinfunction "1_1") (pintype "passive"))
      (node (ref "C4") (pin "1") (pinfunction "1_1") (pintype "passive"))
      (node (ref "C5") (pin "1") (pinfunction "1_1") (pintype "passive"))
      (node (ref "C6") (pin "1") (pinfunction "1_1") (pintype "passive"))
      (node (ref "C7") (pin "1") (pinfunction "1_1") (pintype "passive"))
      (node (ref "C8") (pin "1") (pinfunction "1_1") (pintype "passive"))
      (node (ref "C9") (pin "2") (pinfunction "2_2") (pintype "passive"))
      (node (ref "D3") (pin "2") (pinfunction "K_2") (pintype "passive"))
      (node (ref "D4") (pin "2") (pinfunction "K_2") (pintype "passive"))
      (node (ref "D5") (pin "1") (pinfunction "A_1") (pintype "passive"))
      (node (ref "D6") (pin "1") (pinfunction "A_1") (pintype "passive"))
      (node (ref "D7") (pin "2") (pinfunction "K_2") (pintype "passive"))
      (node (ref "J1") (pin "2") (pinfunction "R_2") (pintype "passive"))
      (node (ref "J1") (pin "3") (pinfunction "S_3") (pintype "passive"))
      (node (ref "P1") (pin "1") (pinfunction "1_1") (pintype "passive"))
      (node (ref "P10") (pin "10") (pinfunction "10_10") (pintype "passive"))
      (node (ref "P10") (pin "12") (pinfunction "12_12") (pintype "passive"))
      (node (ref "P10") (pin "2") (pinfunction "2_2") (pintype "passive"))
      (node (ref "P10") (pin "4") (pinfunction "4_4") (pintype "passive"))
      (node (ref "P10") (pin "6") (pinfunction "6_6") (pintype "passive"))
      (node (ref "P10") (pin "8") (pinfunction "8_8") (pintype "passive"))
      (node (ref "P11") (pin "2") (pinfunction "2_2") (pintype "passive"))
      (node (ref "P12") (pin "2") (pinfunction "2_2") (pintype "passive"))
      (node (ref "P13") (pin "14") (pinfunction "GND_14") (pintype "passive"))
      (node (ref "P13") (pin "20") (pinfunction "GND_20") (pintype "passive"))
      (node (ref "P13") (pin "25") (pinfunction "GND_25") (pintype "passive"))
      (node (ref "P13") (pin "30") (pinfunction "GND_30") (pintype "passive"))
      (node (ref "P13") (pin "34") (pinfunction "GND_34") (pintype "passive"))
      (node (ref "P13") (pin "39") (pinfunction "GND_39") (pintype "passive"))
      (node (ref "P13") (pin "6") (pinfunction "GND_6") (pintype "passive"))
      (node (ref "P13") (pin "9") (pinfunction "GND_9") (pintype "passive"))
      (node (ref "P14") (pin "14") (pinfunction "GND_14") (pintype "passive"))
      (node (ref "P14") (pin "20") (pinfunction "GND_20") (pintype "passive"))
      (node (ref "P14") (pin "25") (pinfunction "GND_25") (pintype "passive"))
      (node (ref "P14") (pin "30") (pinfunction "GND_30") (pintype "passive"))
      (node (ref "P14") (pin "34") (pinfunction "GND_34") (pintype "passive"))
      (node (ref "P14") (pin "39") (pinfunction "GND_39") (pintype "passive"))
      (node (ref "P14") (pin "6") (pinfunction "GND_6") (pintype "passive"))
      (node (ref "P14") (pin "9") (pinfunction "GND_9") (pintype "passive"))
      (node (ref "P15") (pin "1") (pinfunction "1_1") (pintype "passive"))
      (node (ref "P17") (pin "1") (pinfunction "1_1") (pintype "passive"))
      (node (ref "P18") (pin "2") (pinfunction "2_2") (pintype "passive"))
      (node (ref "P2") (pin "1") (pinfunction "1_1") (pintype "passive"))
      (node (ref "P3") (pin "1") (pinfunction "1_1") (pintype "passive"))
      (node (ref "P6") (pin "1") (pinfunction "1_1") (pintype "passive"))
      (node (ref "P7") (pin "1") (pinfunction "1_1") (pintype "passive"))
      (node (ref "P8") (pin "1") (pinfunction "1_1") (pintype "passive"))
      (node (ref "P9") (pin "1") (pinfunction "1_1") (pintype "passive"))
      (node (ref "Q1") (pin "2") (pinfunction "E_2") (pintype "passive"))
      (node (ref "R10") (pin "1") (pinfunction "1_1") (pintype "passive"))
      (node (ref "R16") (pin "1") (pinfunction "1_1") (pintype "passive"))
      (node (ref "R17") (pin "1") (pinfunction "1_1") (pintype "passive"))
      (node (ref "R18") (pin "1") (pinfunction "1_1") (pintype "passive"))
      (node (ref "R8") (pin "1") (pinfunction "1_1") (pintype "passive"))
      (node (ref "R9") (pin "1") (pinfunction "1_1") (pintype "passive"))
      (node (ref "RP1") (pin "1") (pinfunction "TOP_1") (pintype "passive"))
      (node (ref "S1") (pin "2") (pinfunction "2_2") (pintype "passive"))
      (node (ref "S2") (pin "2") (pinfunction "2_2") (pintype "passive"))
      (node (ref "S3") (pin "2") (pinfunction "2_2") (pintype "passive"))
      (node (ref "S4") (pin "2") (pinfunction "2_2") (pintype "passive"))
      (node (ref "U1") (pin "12") (pinfunction "VSSA_12") (pintype "passive"))
      (node (ref "U1") (pin "18") (pinfunction "VSS_4_18") (pintype "passive"))
      (node (ref "U1") (pin "31") (pinfunction "VSS_1_31") (pintype "passive"))
      (node (ref "U1") (pin "47") (pinfunction "VSS_2_47") (pintype "passive"))
      (node (ref "U1") (pin "63") (pinfunction "VSS_3_63") (pintype "passive"))
      (node (ref "U2") (pin "10") (pinfunction "PGND2_10") (pintype "passive"))
      (node (ref "U2") (pin "18") (pinfunction "GND_18") (pintype "passive"))
      (node (ref "U2") (pin "3") (pinfunction "PGND1_3") (pintype "passive"))
      (node (ref "U2") (pin "4") (pinfunction "PGND1_4") (pintype "passive"))
      (node (ref "U2") (pin "9") (pinfunction "PGND2_9") (pintype "passive"))
      (node (ref "U3") (pin "1") (pinfunction "GND_1") (pintype "passive"))
      (node (ref "U4") (pin "3") (pinfunction "GND_3") (pintype "passive"))
      (node (ref "U7") (pin "1") (pinfunction "GND_1") (pintype "power_in"))
      (node (ref "U8") (pin "7") (pinfunction "GND_7") (pintype "passive"))
      (node (ref "U9") (pin "7") (pinfunction "GND_7") (pintype "passive"))
    )
    (net (code "85") (name "Net-(C29-Pad1)") (class "Default")
      (node (ref "C29") (pin "1") (pinfunction "1_1") (pintype "passive"))
      (node (ref "R16") (pin "2") (pinfunction "2_2") (pintype "passive"))
    )
    (net (code "86") (name "Net-(D1-K)") (class "Default")
      (node (ref "D1") (pin "2") (pinfunction "K_2") (pintype "passive"))
      (node (ref "R5") (pin "1") (pinfunction "1_1") (pintype "passive"))
    )
    (net (code "87") (name "Net-(D2-K)") (class "Default")
      (node (ref "D2") (pin "2") (pinfunction "K_2") (pintype "passive"))
      (node (ref "R7") (pin "1") (pinfunction "1_1") (pintype "passive"))
    )
    (net (code "88") (name "Net-(D3-A)") (class "Default")
      (node (ref "D3") (pin "1") (pinfunction "A_1") (pintype "passive"))
      (node (ref "R11") (pin "2") (pinfunction "2_2") (pintype "passive"))
    )
    (net (code "89") (name "Net-(D4-A)") (class "Default")
      (node (ref "D4") (pin "1") (pinfunction "A_1") (pintype "passive"))
      (node (ref "R13") (pin "2") (pinfunction "2_2") (pintype "passive"))
    )
    (net (code "90") (name "Net-(D5-K)") (class "Default")
      (node (ref "C22") (pin "1") (pinfunction "1_1") (pintype "passive"))
      (node (ref "D5") (pin "2") (pinfunction "K_2") (pintype "passive"))
      (node (ref "L1") (pin "1") (pinfunction "1_1") (pintype "passive"))
      (node (ref "U8") (pin "8") (pinfunction "PH_8") (pintype "passive"))
    )
    (net (code "91") (name "Net-(F1-Pad1)") (class "Default")
      (node (ref "F1") (pin "1") (pinfunction "1_1") (pintype "passive"))
      (node (ref "S5") (pin "1") (pinfunction "1_1") (pintype "passive"))
    )
    (net (code "92") (name "Net-(J1-T)") (class "Default")
      (node (ref "J1") (pin "1") (pinfunction "T_1") (pintype "passive"))
      (node (ref "P15") (pin "2") (pinfunction "2_2") (pintype "passive"))
      (node (ref "S5") (pin "2") (pinfunction "2_2") (pintype "passive"))
    )
    (net (code "93") (name "Net-(Q1-B)") (class "Default")
      (node (ref "Q1") (pin "1") (pinfunction "B_1") (pintype "passive"))
      (node (ref "R6") (pin "2") (pinfunction "2_2") (pintype "passive"))
      (node (ref "R8") (pin "2") (pinfunction "2_2") (pintype "passive"))
    )
    (net (code "94") (name "Net-(Q1-C)") (class "Default")
      (node (ref "LS1") (pin "2") (pinfunction "2_2") (pintype "passive"))
      (node (ref "Q1") (pin "3") (pinfunction "C_3") (pintype "passive"))
    )
    (net (code "95") (name "Net-(RP1-TAP)") (class "Default")
      (node (ref "R12") (pin "2") (pinfunction "2_2") (pintype "passive"))
      (node (ref "RP1") (pin "2") (pinfunction "TAP_2") (pintype "passive"))
      (node (ref "U5") (pin "1") (pinfunction "ADJ_1") (pintype "passive"))
    )
    (net (code "96") (name "Net-(U1-BOOT0)") (class "Default")
      (node (ref "R10") (pin "2") (pinfunction "2_2") (pintype "passive"))
      (node (ref "U1") (pin "60") (pinfunction "BOOT0_60") (pintype "passive"))
    )
    (net (code "97") (name "Net-(U1-PB2{slash}BOOT1)") (class "Default")
      (node (ref "R9") (pin "2") (pinfunction "2_2") (pintype "passive"))
      (node (ref "U1") (pin "28") (pinfunction "PB2/BOOT1_28") (pintype "passive"))
    )
    (net (code "98") (name "Net-(U1-PB13{slash}SPI2_SCK{slash}USART3_CTS)") (class "Default")
      (node (ref "R21") (pin "1") (pinfunction "1_1") (pintype "passive"))
      (node (ref "U1") (pin "34") (pinfunction "PB13/SPI2_SCK/USART3_CTS_34") (pintype "passive"))
    )
    (net (code "99") (name "Net-(U1-PD0{slash}OSC_IN)") (class "Default")
      (node (ref "C1") (pin "1") (pinfunction "1_1") (pintype "passive"))
      (node (ref "R1") (pin "2") (pinfunction "2_2") (pintype "passive"))
      (node (ref "U1") (pin "5") (pinfunction "PD0/OSC_IN_5") (pintype "passive"))
      (node (ref "Y1") (pin "2") (pinfunction "OSC2_2") (pintype "passive"))
    )
    (net (code "100") (name "Net-(U1-PD1{slash}OSC_OUT)") (class "Default")
      (node (ref "C2") (pin "1") (pinfunction "1_1") (pintype "passive"))
      (node (ref "R1") (pin "1") (pinfunction "1_1") (pintype "passive"))
      (node (ref "U1") (pin "6") (pinfunction "PD1/OSC_OUT_6") (pintype "passive"))
      (node (ref "Y1") (pin "1") (pinfunction "OSC1_1") (pintype "passive"))
    )
    (net (code "101") (name "Net-(U1-~{NRST})") (class "Default")
      (node (ref "C12") (pin "2") (pinfunction "2_2") (pintype "passive"))
      (node (ref "S4") (pin "1") (pinfunction "1_1") (pintype "passive"))
      (node (ref "U1") (pin "7") (pinfunction "~{NRST}_7") (pintype "passive"))
    )
    (net (code "102") (name "Net-(U8-BOOT)") (class "Default")
      (node (ref "C22") (pin "2") (pinfunction "2_2") (pintype "passive"))
      (node (ref "U8") (pin "1") (pinfunction "BOOT_1") (pintype "passive"))
    )
    (net (code "103") (name "Net-(U8-COMP)") (class "Default")
      (node (ref "C29") (pin "2") (pinfunction "2_2") (pintype "passive"))
      (node (ref "U8") (pin "6") (pinfunction "COMP_6") (pintype "passive"))
    )
    (net (code "104") (name "Net-(U8-EN)") (class "Default")
      (node (ref "R15") (pin "1") (pinfunction "1_1") (pintype "passive"))
      (node (ref "R18") (pin "2") (pinfunction "2_2") (pintype "passive"))
      (node (ref "U8") (pin "3") (pinfunction "EN_3") (pintype "passive"))
    )
    (net (code "105") (name "Net-(U8-SS)") (class "Default")
      (node (ref "C30") (pin "2") (pinfunction "2_2") (pintype "passive"))
      (node (ref "U8") (pin "4") (pinfunction "SS_4") (pintype "passive"))
    )
    (net (code "106") (name "Net-(U8-Vsense)") (class "Default")
      (node (ref "R14") (pin "1") (pinfunction "1_1") (pintype "passive"))
      (node (ref "R17") (pin "2") (pinfunction "2_2") (pintype "passive"))
      (node (ref "U8") (pin "5") (pinfunction "Vsense_5") (pintype "passive"))
    )
    (net (code "107") (name "VETEER") (class "Default")
      (node (ref "C14") (pin "2") (pinfunction "2_2") (pintype "passive"))
      (node (ref "C15") (pin "1") (pinfunction "1_1") (pintype "passive"))
      (node (ref "C3") (pin "1") (pinfunction "1_1") (pintype "passive"))
      (node (ref "P1") (pin "2") (pinfunction "2_2") (pintype "passive"))
      (node (ref "P10") (pin "11") (pinfunction "11_11") (pintype "passive"))
      (node (ref "P10") (pin "9") (pinfunction "9_9") (pintype "passive"))
      (node (ref "P11") (pin "1") (pinfunction "1_1") (pintype "passive"))
      (node (ref "P17") (pin "2") (pinfunction "2_2") (pintype "passive"))
      (node (ref "P2") (pin "2") (pinfunction "2_2") (pintype "passive"))
      (node (ref "P3") (pin "2") (pinfunction "2_2") (pintype "passive"))
      (node (ref "P6") (pin "2") (pinfunction "2_2") (pintype "passive"))
      (node (ref "P7") (pin "2") (pinfunction "2_2") (pintype "passive"))
      (node (ref "P8") (pin "2") (pinfunction "2_2") (pintype "passive"))
      (node (ref "R11") (pin "1") (pinfunction "1_1") (pintype "passive"))
      (node (ref "R12") (pin "1") (pinfunction "1_1") (pintype "passive"))
      (node (ref "U5") (pin "2") (pinfunction "OUT_2") (pintype "passive"))
      (node (ref "U5") (pin "4") (pinfunction "OUT_4") (pintype "passive"))
    )
    (net (code "108") (name "unconnected-(RP1-BOT-Pad3)") (class "Default")
      (node (ref "RP1") (pin "3") (pinfunction "BOT_3") (pintype "passive"))
    )
    (net (code "109") (name "unconnected-(S5-Pad3)") (class "Default")
      (node (ref "S5") (pin "3") (pinfunction "3_3") (pintype "passive"))
    )
    (net (code "110") (name "unconnected-(U9-GPIO0-Pad3)") (class "Default")
      (node (ref "U9") (pin "3") (pinfunction "GPIO0_3") (pintype "passive"))
    )
    (net (code "111") (name "unconnected-(U9-GPIO2-Pad5)") (class "Default")
      (node (ref "U9") (pin "5") (pinfunction "GPIO2_5") (pintype "passive"))
    )
  )
)
